# YARO.net
KiCad netlist of a schematic drawn in EAGLE
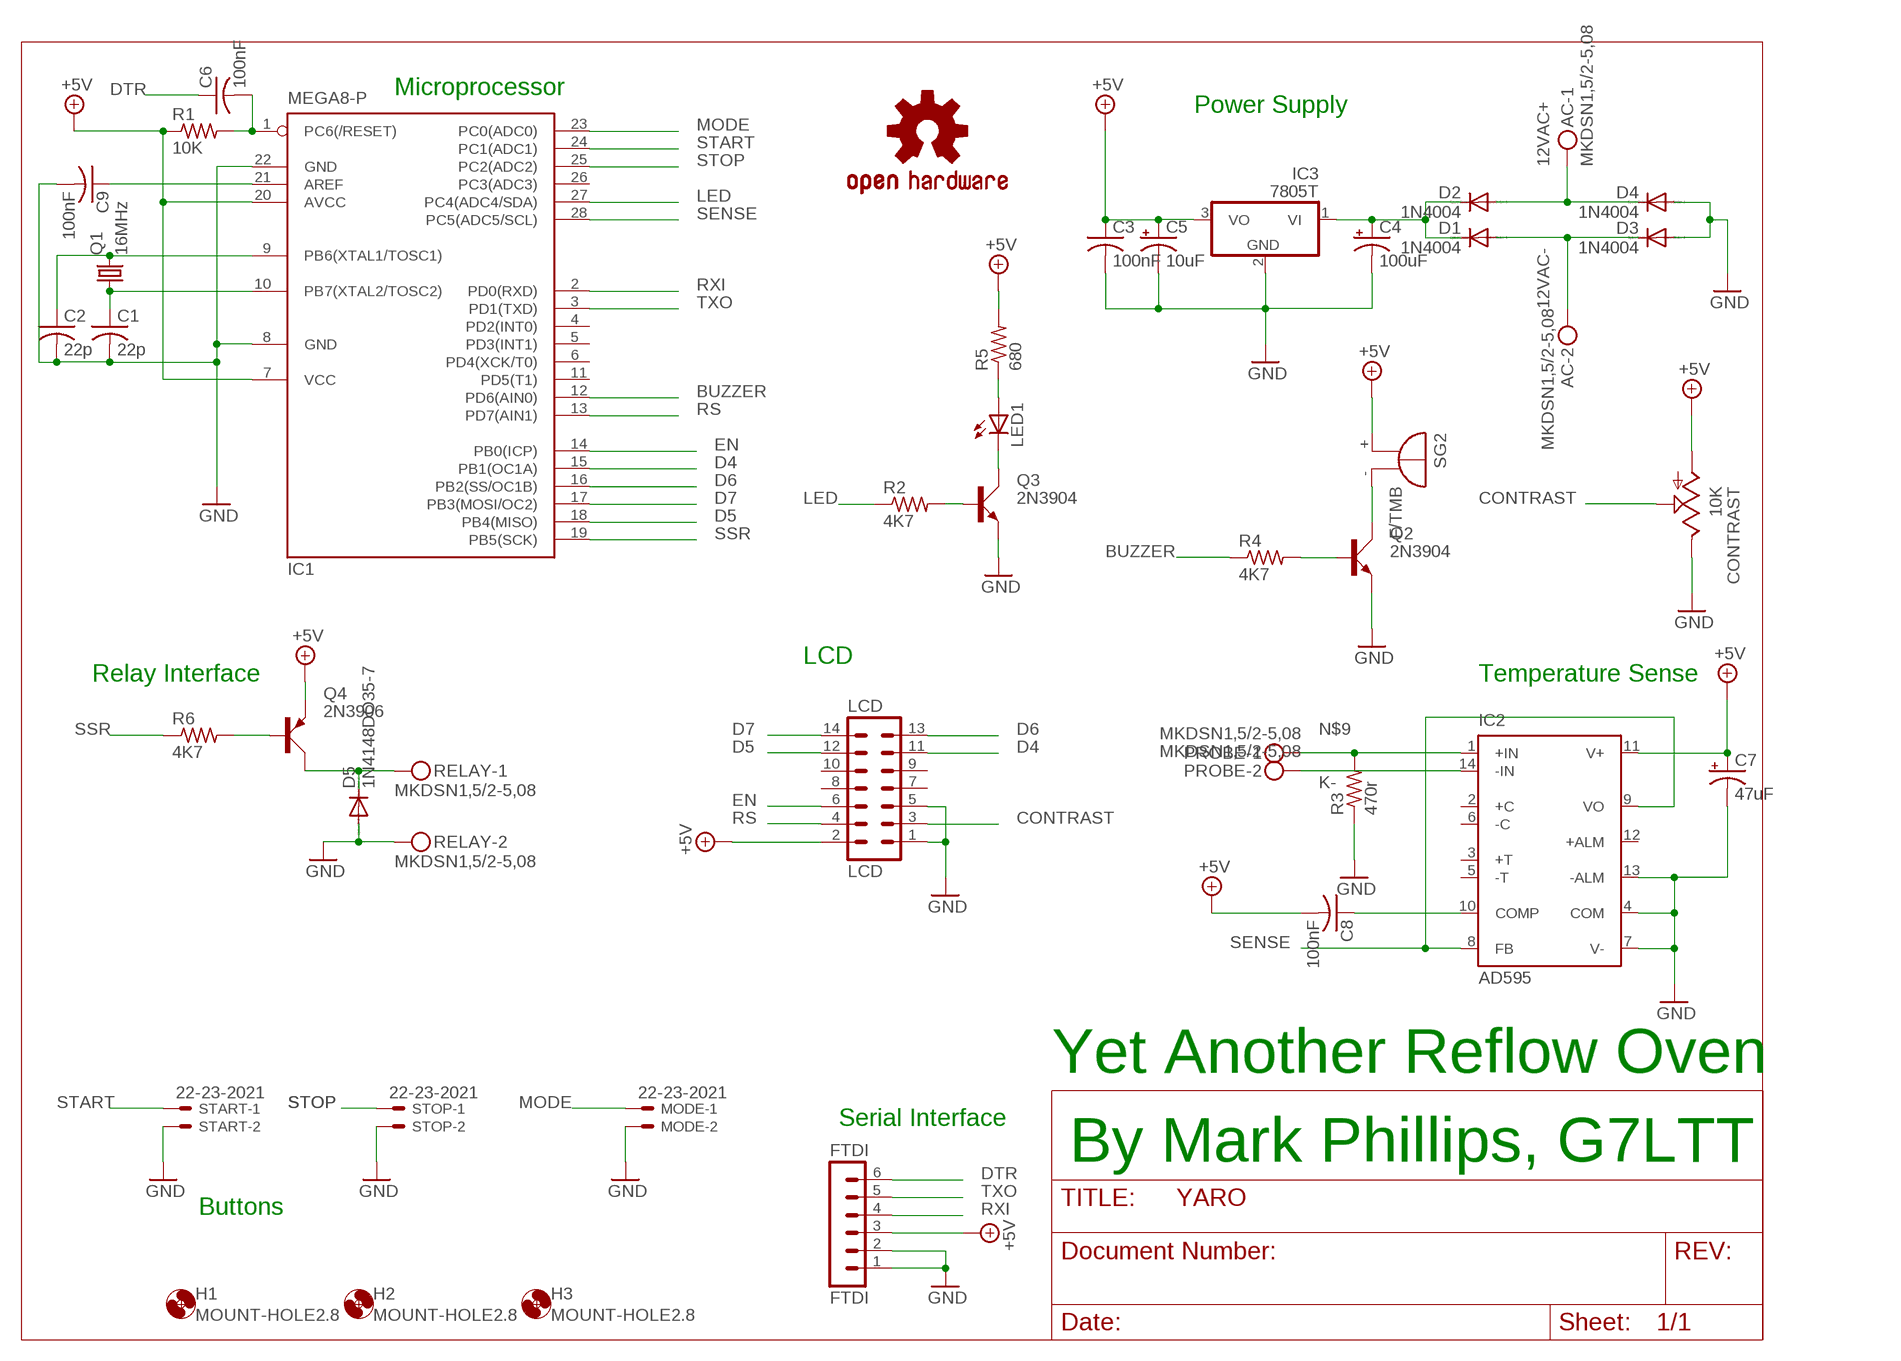
[diagram p0: schematic, sheet 1]

(export (version "E")
  (design (tool "Eeschema 10.0.6"))
  (components
    (comp (ref "AC")
      (value "MKDSN1,5/2-5,08")
      (footprint "eagle-import:MKDSN1,5_2-5,08")
      (libsource (lib "eagle-import") (part "MKDSN1,5/2-5,08"))
    )
    (comp (ref "C1")
      (value "22p")
      (footprint "eagle-import:C025-025X050")
      (libsource (lib "eagle-import") (part "C-US025-025X050"))
    )
    (comp (ref "C2")
      (value "22p")
      (footprint "eagle-import:C025-025X050")
      (libsource (lib "eagle-import") (part "C-US025-025X050"))
    )
    (comp (ref "C3")
      (value "100nF")
      (footprint "eagle-import:C025-025X050")
      (libsource (lib "eagle-import") (part "C-US025-025X050"))
    )
    (comp (ref "C4")
      (value "100uF")
      (footprint "eagle-import:E2,5-6")
      (libsource (lib "eagle-import") (part "CPOL-USE2.5-6"))
    )
    (comp (ref "C5")
      (value "10uF")
      (footprint "eagle-import:E2,5-5")
      (libsource (lib "eagle-import") (part "CPOL-USE2.5-5"))
    )
    (comp (ref "C6")
      (value "100nF")
      (footprint "eagle-import:C025-025X050")
      (libsource (lib "eagle-import") (part "C-US025-025X050"))
    )
    (comp (ref "C7")
      (value "47uF")
      (footprint "eagle-import:E2,5-5")
      (libsource (lib "eagle-import") (part "CPOL-USE2.5-5"))
    )
    (comp (ref "C8")
      (value "100nF")
      (footprint "eagle-import:C025-025X050")
      (libsource (lib "eagle-import") (part "C-US025-025X050"))
    )
    (comp (ref "C9")
      (value "100nF")
      (footprint "eagle-import:C025-025X050")
      (libsource (lib "eagle-import") (part "C-US025-025X050"))
    )
    (comp (ref "CONTRAST")
      (value "10K")
      (footprint "eagle-import:CA6V")
      (libsource (lib "eagle-import") (part "TRIM_US-CA6V"))
    )
    (comp (ref "D1")
      (value "1N4004")
      (footprint "eagle-import:DO41-10")
      (libsource (lib "eagle-import") (part "1N4004"))
    )
    (comp (ref "D2")
      (value "1N4004")
      (footprint "eagle-import:DO41-10")
      (libsource (lib "eagle-import") (part "1N4004"))
    )
    (comp (ref "D3")
      (value "1N4004")
      (footprint "eagle-import:DO41-10")
      (libsource (lib "eagle-import") (part "1N4004"))
    )
    (comp (ref "D4")
      (value "1N4004")
      (footprint "eagle-import:DO41-10")
      (libsource (lib "eagle-import") (part "1N4004"))
    )
    (comp (ref "D5")
      (value "1N4148DO35-7")
      (footprint "eagle-import:DO35-7")
      (libsource (lib "eagle-import") (part "1N4148DO35-7"))
    )
    (comp (ref "FTDI")
      (value "FTDI")
      (footprint "eagle-import:MA06-1")
      (libsource (lib "eagle-import") (part "MA06-1"))
    )
    (comp (ref "H1")
      (value "MOUNT-HOLE2.8")
      (footprint "eagle-import:2,8")
      (libsource (lib "eagle-import") (part "MOUNT-HOLE2.8"))
    )
    (comp (ref "H2")
      (value "MOUNT-HOLE2.8")
      (footprint "eagle-import:2,8")
      (libsource (lib "eagle-import") (part "MOUNT-HOLE2.8"))
    )
    (comp (ref "H3")
      (value "MOUNT-HOLE2.8")
      (footprint "eagle-import:2,8")
      (libsource (lib "eagle-import") (part "MOUNT-HOLE2.8"))
    )
    (comp (ref "IC1")
      (value "MEGA8-P")
      (footprint "eagle-import:DIL28-3")
      (libsource (lib "eagle-import") (part "MEGA8-P"))
    )
    (comp (ref "IC2")
      (value "AD595")
      (footprint "eagle-import:DIL14")
      (fields (field (name "MPN") "AD595AQ"))
      (libsource (lib "eagle-import") (part "AD595"))
    )
    (comp (ref "IC3")
      (value "7805T")
      (footprint "eagle-import:TO220H")
      (libsource (lib "eagle-import") (part "78T05"))
    )
    (comp (ref "LCD")
      (value "LCD")
      (footprint "eagle-import:MA07-2")
      (libsource (lib "eagle-import") (part "MA07-2"))
    )
    (comp (ref "LED1")
      (value "LED5MM")
      (footprint "eagle-import:LED5MM")
      (libsource (lib "eagle-import") (part "LED5MM"))
    )
    (comp (ref "LOGO2")
      (value "OSHW-LOGOL")
      (footprint "eagle-import:OSHW-LOGO-L")
      (libsource (lib "eagle-import") (part "OSHW-LOGOL"))
    )
    (comp (ref "MODE")
      (value "22-23-2021")
      (footprint "eagle-import:22-23-2021")
      (fields (field (name "MF") "MOLEX"))
      (libsource (lib "eagle-import") (part "22-23-2021"))
    )
    (comp (ref "PROBE")
      (value "MKDSN1,5/2-5,08")
      (footprint "eagle-import:MKDSN1,5_2-5,08")
      (libsource (lib "eagle-import") (part "MKDSN1,5/2-5,08"))
    )
    (comp (ref "Q1")
      (value "16MHz")
      (footprint "eagle-import:HC49_S")
      (libsource (lib "eagle-import") (part "CRYSTALHC49S"))
    )
    (comp (ref "Q2")
      (value "2N3904")
      (footprint "eagle-import:TO92D")
      (libsource (lib "eagle-import") (part "2N3904"))
    )
    (comp (ref "Q3")
      (value "2N3904")
      (footprint "eagle-import:TO92D")
      (libsource (lib "eagle-import") (part "2N3904"))
    )
    (comp (ref "Q4")
      (value "2N3906")
      (footprint "eagle-import:TO92D")
      (libsource (lib "eagle-import") (part "2N3906"))
    )
    (comp (ref "R1")
      (value "10K")
      (footprint "eagle-import:0204_7")
      (libsource (lib "eagle-import") (part "R-US_0204/7"))
    )
    (comp (ref "R2")
      (value "4K7")
      (footprint "eagle-import:0204_7")
      (libsource (lib "eagle-import") (part "R-US_0204/7"))
    )
    (comp (ref "R3")
      (value "470r")
      (footprint "eagle-import:0204_7")
      (libsource (lib "eagle-import") (part "R-US_0204/7"))
    )
    (comp (ref "R4")
      (value "4K7")
      (footprint "eagle-import:0204_7")
      (libsource (lib "eagle-import") (part "R-US_0204/7"))
    )
    (comp (ref "R5")
      (value "680")
      (footprint "eagle-import:0204_7")
      (libsource (lib "eagle-import") (part "R-US_0204/7"))
    )
    (comp (ref "R6")
      (value "4K7")
      (footprint "eagle-import:0204_7")
      (libsource (lib "eagle-import") (part "R-US_0204/7"))
    )
    (comp (ref "RELAY")
      (value "MKDSN1,5/2-5,08")
      (footprint "eagle-import:MKDSN1,5_2-5,08")
      (libsource (lib "eagle-import") (part "MKDSN1,5/2-5,08"))
    )
    (comp (ref "SG2")
      (value "F/TMB")
      (footprint "eagle-import:F_TMB")
      (libsource (lib "eagle-import") (part "F/TMB"))
    )
    (comp (ref "START")
      (value "22-23-2021")
      (footprint "eagle-import:22-23-2021")
      (fields (field (name "MF") "MOLEX"))
      (libsource (lib "eagle-import") (part "22-23-2021"))
    )
    (comp (ref "STOP")
      (value "22-23-2021")
      (footprint "eagle-import:22-23-2021")
      (fields (field (name "MF") "MOLEX"))
      (libsource (lib "eagle-import") (part "22-23-2021"))
    )
  )
  (nets
    (net (code "1") (name "+5V") (class "Default")
      (node (ref "C3") (pin "1") (pinfunction "1_1") (pintype "passive"))
      (node (ref "C5") (pin "+") (pinfunction "+_+") (pintype "passive"))
      (node (ref "C7") (pin "+") (pinfunction "+_+") (pintype "passive"))
      (node (ref "C8") (pin "2") (pinfunction "2_2") (pintype "passive"))
      (node (ref "CONTRAST") (pin "A") (pinfunction "A_A") (pintype "passive"))
      (node (ref "FTDI") (pin "3") (pinfunction "3_3") (pintype "passive"))
      (node (ref "IC1") (pin "20") (pinfunction "AVCC_20") (pintype "power_in"))
      (node (ref "IC1") (pin "7") (pinfunction "VCC_7") (pintype "power_in"))
      (node (ref "IC2") (pin "11") (pinfunction "V+_11") (pintype "power_in"))
      (node (ref "IC3") (pin "3") (pinfunction "VO_3") (pintype "passive"))
      (node (ref "LCD") (pin "2") (pinfunction "2_2") (pintype "passive"))
      (node (ref "Q4") (pin "E") (pinfunction "E_E") (pintype "passive"))
      (node (ref "R1") (pin "1") (pinfunction "1_1") (pintype "passive"))
      (node (ref "R5") (pin "2") (pinfunction "2_2") (pintype "passive"))
      (node (ref "SG2") (pin "+") (pinfunction "+_+") (pintype "passive"))
    )
    (net (code "2") (name "/12VAC+") (class "Default")
      (node (ref "AC") (pin "1") (pinfunction "KL_1") (pintype "passive"))
      (node (ref "D2") (pin "A") (pinfunction "A_A") (pintype "passive"))
      (node (ref "D4") (pin "C") (pinfunction "C_C") (pintype "passive"))
    )
    (net (code "3") (name "/12VAC-") (class "Default")
      (node (ref "AC") (pin "2") (pinfunction "KL_2") (pintype "passive"))
      (node (ref "D1") (pin "A") (pinfunction "A_A") (pintype "passive"))
      (node (ref "D3") (pin "C") (pinfunction "C_C") (pintype "passive"))
    )
    (net (code "4") (name "/BUZZER") (class "Default")
      (node (ref "IC1") (pin "12") (pinfunction "PD6(AIN0)_12") (pintype "bidirectional"))
      (node (ref "R4") (pin "1") (pinfunction "1_1") (pintype "passive"))
    )
    (net (code "5") (name "/CONTRAST") (class "Default")
      (node (ref "CONTRAST") (pin "S") (pinfunction "S_S") (pintype "passive"))
      (node (ref "LCD") (pin "3") (pinfunction "3_3") (pintype "passive"))
    )
    (net (code "6") (name "/D4") (class "Default")
      (node (ref "IC1") (pin "15") (pinfunction "PB1(OC1A)_15") (pintype "bidirectional"))
      (node (ref "LCD") (pin "11") (pinfunction "11_11") (pintype "passive"))
    )
    (net (code "7") (name "/D5") (class "Default")
      (node (ref "IC1") (pin "18") (pinfunction "PB4(MISO)_18") (pintype "bidirectional"))
      (node (ref "LCD") (pin "12") (pinfunction "12_12") (pintype "passive"))
    )
    (net (code "8") (name "/D6") (class "Default")
      (node (ref "IC1") (pin "16") (pinfunction "PB2(SS/OC1B)_16") (pintype "bidirectional"))
      (node (ref "LCD") (pin "13") (pinfunction "13_13") (pintype "passive"))
    )
    (net (code "9") (name "/D7") (class "Default")
      (node (ref "IC1") (pin "17") (pinfunction "PB3(MOSI/OC2)_17") (pintype "bidirectional"))
      (node (ref "LCD") (pin "14") (pinfunction "14_14") (pintype "passive"))
    )
    (net (code "10") (name "/DTR") (class "Default")
      (node (ref "C6") (pin "1") (pinfunction "1_1") (pintype "passive"))
      (node (ref "FTDI") (pin "6") (pinfunction "6_6") (pintype "passive"))
    )
    (net (code "11") (name "/EN") (class "Default")
      (node (ref "IC1") (pin "14") (pinfunction "PB0(ICP)_14") (pintype "bidirectional"))
      (node (ref "LCD") (pin "6") (pinfunction "6_6") (pintype "passive"))
    )
    (net (code "12") (name "/K-") (class "Default")
      (node (ref "IC2") (pin "14") (pinfunction "-IN_14") (pintype "input"))
      (node (ref "PROBE") (pin "2") (pinfunction "KL_2") (pintype "passive"))
    )
    (net (code "13") (name "/LED") (class "Default")
      (node (ref "IC1") (pin "27") (pinfunction "PC4(ADC4/SDA)_27") (pintype "bidirectional"))
      (node (ref "R2") (pin "1") (pinfunction "1_1") (pintype "passive"))
    )
    (net (code "14") (name "/MODE") (class "Default")
      (node (ref "IC1") (pin "23") (pinfunction "PC0(ADC0)_23") (pintype "bidirectional"))
      (node (ref "MODE") (pin "1") (pinfunction "S_1") (pintype "passive"))
    )
    (net (code "15") (name "/N$9") (class "Default")
      (node (ref "IC2") (pin "1") (pinfunction "+IN_1") (pintype "input"))
      (node (ref "PROBE") (pin "1") (pinfunction "KL_1") (pintype "passive"))
      (node (ref "R3") (pin "2") (pinfunction "2_2") (pintype "passive"))
    )
    (net (code "16") (name "/RS") (class "Default")
      (node (ref "IC1") (pin "13") (pinfunction "PD7(AIN1)_13") (pintype "bidirectional"))
      (node (ref "LCD") (pin "4") (pinfunction "4_4") (pintype "passive"))
    )
    (net (code "17") (name "/RXI") (class "Default")
      (node (ref "FTDI") (pin "4") (pinfunction "4_4") (pintype "passive"))
      (node (ref "IC1") (pin "2") (pinfunction "PD0(RXD)_2") (pintype "bidirectional"))
    )
    (net (code "18") (name "/SENSE") (class "Default")
      (node (ref "IC1") (pin "28") (pinfunction "PC5(ADC5/SCL)_28") (pintype "bidirectional"))
      (node (ref "IC2") (pin "8") (pinfunction "FB_8") (pintype "passive"))
      (node (ref "IC2") (pin "9") (pinfunction "VO_9") (pintype "output"))
    )
    (net (code "19") (name "/SSR") (class "Default")
      (node (ref "IC1") (pin "19") (pinfunction "PB5(SCK)_19") (pintype "bidirectional"))
      (node (ref "R6") (pin "1") (pinfunction "1_1") (pintype "passive"))
    )
    (net (code "20") (name "/START") (class "Default")
      (node (ref "IC1") (pin "24") (pinfunction "PC1(ADC1)_24") (pintype "bidirectional"))
      (node (ref "START") (pin "1") (pinfunction "S_1") (pintype "passive"))
    )
    (net (code "21") (name "/STOP") (class "Default")
      (node (ref "IC1") (pin "25") (pinfunction "PC2(ADC2)_25") (pintype "bidirectional"))
      (node (ref "STOP") (pin "1") (pinfunction "S_1") (pintype "passive"))
    )
    (net (code "22") (name "/TXO") (class "Default")
      (node (ref "FTDI") (pin "5") (pinfunction "5_5") (pintype "passive"))
      (node (ref "IC1") (pin "3") (pinfunction "PD1(TXD)_3") (pintype "bidirectional"))
    )
    (net (code "23") (name "GND") (class "Default")
      (node (ref "C1") (pin "2") (pinfunction "2_2") (pintype "passive"))
      (node (ref "C2") (pin "2") (pinfunction "2_2") (pintype "passive"))
      (node (ref "C3") (pin "2") (pinfunction "2_2") (pintype "passive"))
      (node (ref "C4") (pin "-") (pinfunction "-_-") (pintype "passive"))
      (node (ref "C5") (pin "-") (pinfunction "-_-") (pintype "passive"))
      (node (ref "C7") (pin "-") (pinfunction "-_-") (pintype "passive"))
      (node (ref "C9") (pin "2") (pinfunction "2_2") (pintype "passive"))
      (node (ref "CONTRAST") (pin "E") (pinfunction "E_E") (pintype "passive"))
      (node (ref "D3") (pin "A") (pinfunction "A_A") (pintype "passive"))
      (node (ref "D4") (pin "A") (pinfunction "A_A") (pintype "passive"))
      (node (ref "D5") (pin "A") (pinfunction "A_A") (pintype "passive"))
      (node (ref "FTDI") (pin "1") (pinfunction "1_1") (pintype "passive"))
      (node (ref "FTDI") (pin "2") (pinfunction "2_2") (pintype "passive"))
      (node (ref "IC1") (pin "22") (pinfunction "GND_22") (pintype "power_in"))
      (node (ref "IC1") (pin "8") (pinfunction "GND_8") (pintype "power_in"))
      (node (ref "IC2") (pin "13") (pinfunction "-ALM_13") (pintype "passive"))
      (node (ref "IC2") (pin "4") (pinfunction "COM_4") (pintype "power_in"))
      (node (ref "IC2") (pin "7") (pinfunction "V-_7") (pintype "power_in"))
      (node (ref "IC3") (pin "2") (pinfunction "GND_2") (pintype "passive"))
      (node (ref "LCD") (pin "1") (pinfunction "1_1") (pintype "passive"))
      (node (ref "LCD") (pin "5") (pinfunction "5_5") (pintype "passive"))
      (node (ref "MODE") (pin "2") (pinfunction "S_2") (pintype "passive"))
      (node (ref "Q2") (pin "E") (pinfunction "E_E") (pintype "passive"))
      (node (ref "Q3") (pin "E") (pinfunction "E_E") (pintype "passive"))
      (node (ref "R3") (pin "1") (pinfunction "1_1") (pintype "passive"))
      (node (ref "RELAY") (pin "2") (pinfunction "KL_2") (pintype "passive"))
      (node (ref "START") (pin "2") (pinfunction "S_2") (pintype "passive"))
      (node (ref "STOP") (pin "2") (pinfunction "S_2") (pintype "passive"))
    )
    (net (code "24") (name "Net-(IC1-AREF)") (class "Default")
      (node (ref "C9") (pin "1") (pinfunction "1_1") (pintype "passive"))
      (node (ref "IC1") (pin "21") (pinfunction "AREF_21") (pintype "passive"))
    )
    (net (code "25") (name "Net-(IC1-PB6(XTAL1{slash}TOSC1))") (class "Default")
      (node (ref "C2") (pin "1") (pinfunction "1_1") (pintype "passive"))
      (node (ref "IC1") (pin "9") (pinfunction "PB6(XTAL1/TOSC1)_9") (pintype "bidirectional"))
      (node (ref "Q1") (pin "2") (pinfunction "2_2") (pintype "passive"))
    )
    (net (code "26") (name "Net-(IC1-PB7(XTAL2{slash}TOSC2))") (class "Default")
      (node (ref "C1") (pin "1") (pinfunction "1_1") (pintype "passive"))
      (node (ref "IC1") (pin "10") (pinfunction "PB7(XTAL2/TOSC2)_10") (pintype "bidirectional"))
      (node (ref "Q1") (pin "1") (pinfunction "1_1") (pintype "passive"))
    )
    (net (code "27") (name "Net-(IC1-PC6({slash}RESET))") (class "Default")
      (node (ref "C6") (pin "2") (pinfunction "2_2") (pintype "passive"))
      (node (ref "IC1") (pin "1") (pinfunction "PC6(/RESET)_1") (pintype "bidirectional"))
      (node (ref "R1") (pin "2") (pinfunction "2_2") (pintype "passive"))
    )
    (net (code "28") (name "Net-(IC2-COMP)") (class "Default")
      (node (ref "C8") (pin "1") (pinfunction "1_1") (pintype "passive"))
      (node (ref "IC2") (pin "10") (pinfunction "COMP_10") (pintype "passive"))
    )
    (net (code "29") (name "Net-(IC3-VI)") (class "Default")
      (node (ref "C4") (pin "+") (pinfunction "+_+") (pintype "passive"))
      (node (ref "D1") (pin "C") (pinfunction "C_C") (pintype "passive"))
      (node (ref "D2") (pin "C") (pinfunction "C_C") (pintype "passive"))
      (node (ref "IC3") (pin "1") (pinfunction "VI_1") (pintype "input"))
    )
    (net (code "30") (name "Net-(LED1-C)") (class "Default")
      (node (ref "LED1") (pin "K") (pinfunction "C_K") (pintype "passive"))
      (node (ref "Q3") (pin "C") (pinfunction "C_C") (pintype "passive"))
    )
    (net (code "31") (name "Net-(LED1-PadA)") (class "Default")
      (node (ref "LED1") (pin "A") (pinfunction "A_A") (pintype "passive"))
      (node (ref "R5") (pin "1") (pinfunction "1_1") (pintype "passive"))
    )
    (net (code "32") (name "Net-(Q2-PadB)") (class "Default")
      (node (ref "Q2") (pin "B") (pinfunction "B_B") (pintype "passive"))
      (node (ref "R4") (pin "2") (pinfunction "2_2") (pintype "passive"))
    )
    (net (code "33") (name "Net-(Q2-PadC)") (class "Default")
      (node (ref "Q2") (pin "C") (pinfunction "C_C") (pintype "passive"))
      (node (ref "SG2") (pin "-") (pinfunction "-_-") (pintype "passive"))
    )
    (net (code "34") (name "Net-(Q3-PadB)") (class "Default")
      (node (ref "Q3") (pin "B") (pinfunction "B_B") (pintype "passive"))
      (node (ref "R2") (pin "2") (pinfunction "2_2") (pintype "passive"))
    )
    (net (code "35") (name "Net-(Q4-PadB)") (class "Default")
      (node (ref "Q4") (pin "B") (pinfunction "B_B") (pintype "passive"))
      (node (ref "R6") (pin "2") (pinfunction "2_2") (pintype "passive"))
    )
    (net (code "36") (name "Net-(RELAYA-KL)") (class "Default")
      (node (ref "D5") (pin "C") (pinfunction "C_C") (pintype "passive"))
      (node (ref "Q4") (pin "C") (pinfunction "C_C") (pintype "passive"))
      (node (ref "RELAY") (pin "1") (pinfunction "KL_1") (pintype "passive"))
    )
    (net (code "37") (name "unconnected-(IC1-PC3(ADC3)-Pad26)") (class "Default")
      (node (ref "IC1") (pin "26") (pinfunction "PC3(ADC3)_26") (pintype "bidirectional"))
    )
    (net (code "38") (name "unconnected-(IC1-PD2(INT0)-Pad4)") (class "Default")
      (node (ref "IC1") (pin "4") (pinfunction "PD2(INT0)_4") (pintype "bidirectional"))
    )
    (net (code "39") (name "unconnected-(IC1-PD3(INT1)-Pad5)") (class "Default")
      (node (ref "IC1") (pin "5") (pinfunction "PD3(INT1)_5") (pintype "bidirectional"))
    )
    (net (code "40") (name "unconnected-(IC1-PD4(XCK{slash}T0)-Pad6)") (class "Default")
      (node (ref "IC1") (pin "6") (pinfunction "PD4(XCK/T0)_6") (pintype "bidirectional"))
    )
    (net (code "41") (name "unconnected-(IC1-PD5(T1)-Pad11)") (class "Default")
      (node (ref "IC1") (pin "11") (pinfunction "PD5(T1)_11") (pintype "bidirectional"))
    )
    (net (code "42") (name "unconnected-(IC2-+ALM-Pad12)") (class "Default")
      (node (ref "IC2") (pin "12") (pinfunction "+ALM_12") (pintype "passive"))
    )
    (net (code "43") (name "unconnected-(IC2-+C-Pad2)") (class "Default")
      (node (ref "IC2") (pin "2") (pinfunction "+C_2") (pintype "input"))
    )
    (net (code "44") (name "unconnected-(IC2-+T-Pad3)") (class "Default")
      (node (ref "IC2") (pin "3") (pinfunction "+T_3") (pintype "passive"))
    )
    (net (code "45") (name "unconnected-(IC2--C-Pad6)") (class "Default")
      (node (ref "IC2") (pin "6") (pinfunction "-C_6") (pintype "input"))
    )
    (net (code "46") (name "unconnected-(IC2--T-Pad5)") (class "Default")
      (node (ref "IC2") (pin "5") (pinfunction "-T_5") (pintype "passive"))
    )
    (net (code "47") (name "unconnected-(LCD-Pad7)") (class "Default")
      (node (ref "LCD") (pin "7") (pinfunction "7_7") (pintype "passive"))
    )
    (net (code "48") (name "unconnected-(LCD-Pad8)") (class "Default")
      (node (ref "LCD") (pin "8") (pinfunction "8_8") (pintype "passive"))
    )
    (net (code "49") (name "unconnected-(LCD-Pad9)") (class "Default")
      (node (ref "LCD") (pin "9") (pinfunction "9_9") (pintype "passive"))
    )
    (net (code "50") (name "unconnected-(LCD-Pad10)") (class "Default")
      (node (ref "LCD") (pin "10") (pinfunction "10_10") (pintype "passive"))
    )
  )
)
